# 7_Accumulator_Indicator.net
KiCad netlist of a schematic drawn in Altium Designer
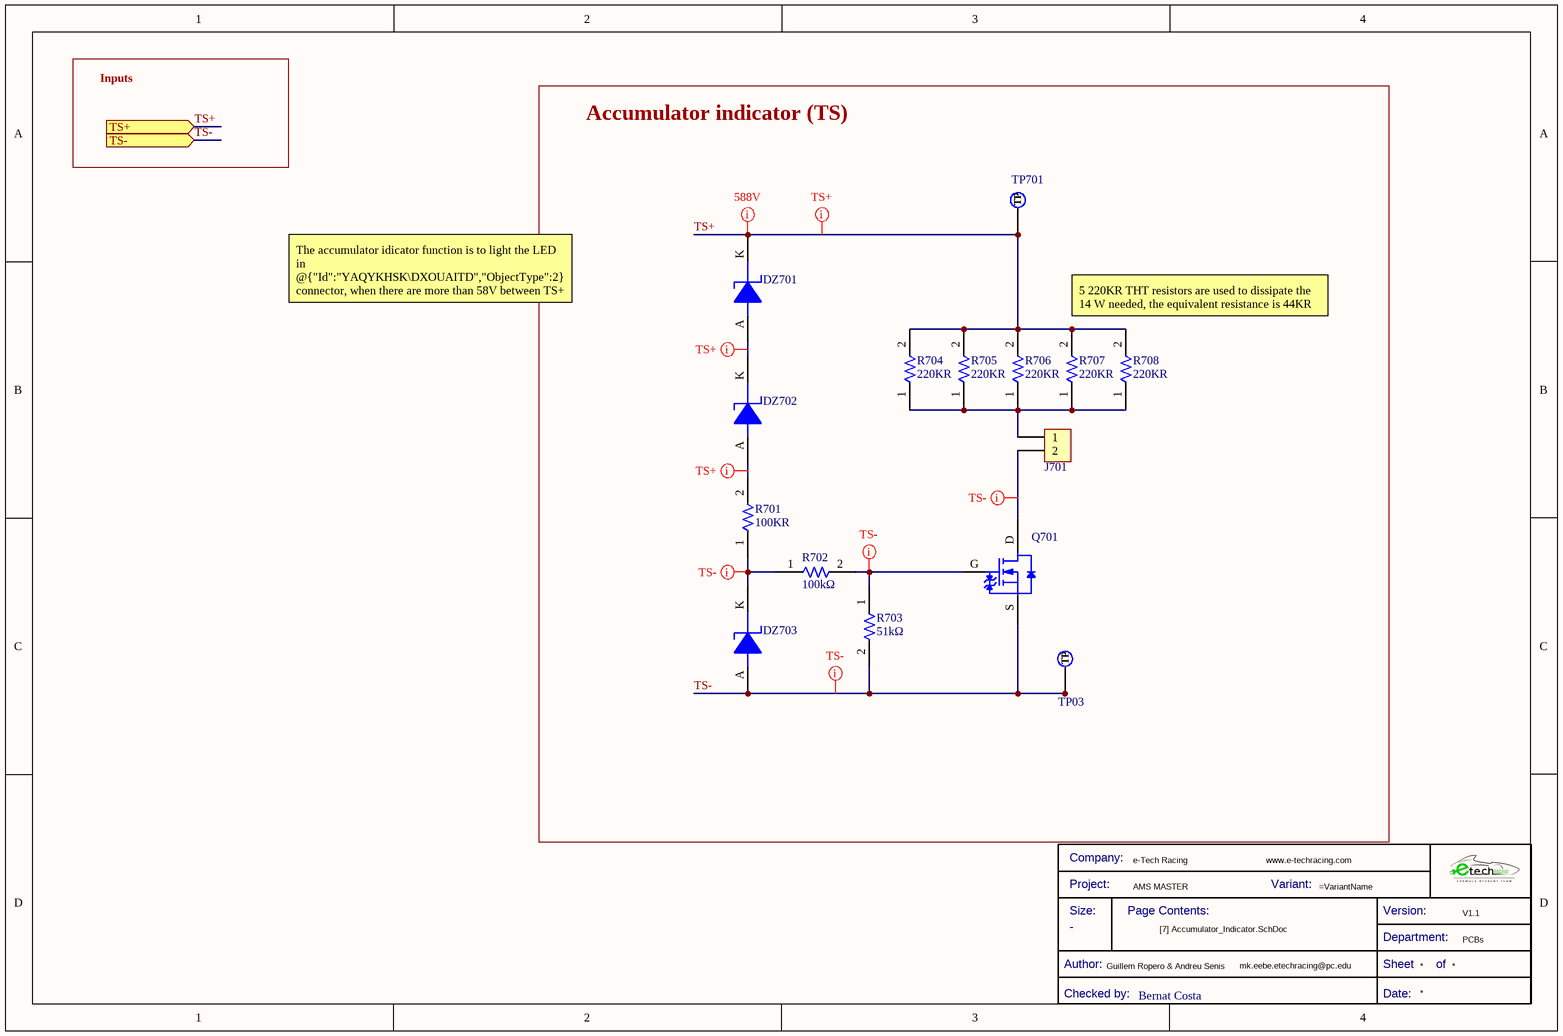
[diagram p0: [7] Accumulator_Indicator.SchDoc]

(export (version "E")
  (design (tool "Eeschema 10.0.6"))
  (components
    (comp (ref "DZ701")
      (value "DZ_24V")
      (footprint "DO214AC")
      (description "1.0 W Zener Diode Voltage Regulator 24 V")
      (fields
        (field (name "MANUFACTURER") "Diodes")
        (field (name "MANUFACTURER PART NUMBER") "BZT52C5V1-7-F")
      )
      (libsource (lib "Semiconductor") (part "DZ_24V"))
    )
    (comp (ref "DZ702")
      (value "DZ_24V")
      (footprint "DO214AC")
      (description "1.0 W Zener Diode Voltage Regulator 24 V")
      (fields
        (field (name "MANUFACTURER") "Diodes")
        (field (name "MANUFACTURER PART NUMBER") "BZT52C5V1-7-F")
      )
      (libsource (lib "Semiconductor") (part "DZ_24V"))
    )
    (comp (ref "DZ703")
      (value "DZ_10V")
      (footprint "SOD123")
      (description "BZT52C5V1 Series 500 mW 10V 10 mA Surface Mount Zener Diode - SOD-123")
      (fields
        (field (name "MANUFACTURER") "Diodes")
        (field (name "MANUFACTURER PART NUMBER") "BZT52C5V1-7-F")
      )
      (libsource (lib "Semiconductor") (part "DZ_10V"))
    )
    (comp (ref "J701")
      (value "105309-2202")
      (footprint "J_NanoFit_1x2_V")
      (fields (field (name "MANUFACTURER") "Molex"))
      (libsource (lib "Electromechanical") (part "J_Nanofit_1x2_V"))
    )
    (comp (ref "Q701")
      (value "IRLR2905")
      (footprint "IRLR2905")
      (description "MOSFET N-CH 55V 42A DPAK")
      (fields
        (field (name "MANUFACTURER") "Infineon")
        (field (name "MANUFACTURER PART NUMBER") "IRLR2905TRPBF")
      )
      (libsource (lib "Semiconductor") (part "TRT-NCH-55V-42A"))
    )
    (comp (ref "R701")
      (value "100KR")
      (footprint "THT_3W_Resistor")
      (libsource (lib "Passives") (part "R100K_3W_THT"))
    )
    (comp (ref "R702")
      (value "CRG1206F100R")
      (footprint "R1206FTK-W")
      (description "Res Thick Film 1206 100 Ohm 1% 0.25W(1/4W) ±200ppm/C Pad SMD T/R")
      (fields
        (field (name "MANUFACTURER") "TE Connectivity")
        (field (name "TOLERANCE") "1%")
        (field (name "RESISTANCE") "100kΩ")
        (field (name ".CREATOR") "AC")
      )
      (libsource (lib "Passives") (part "R100-1206FTK"))
    )
    (comp (ref "R703")
      (value "CRCW120610K0FKEA")
      (footprint "R1206FTK-W")
      (description "Res Thick Film 1206 51K Ohm 1% 1/4W ±100ppm/°C Molded SMD SMD Punched Carrier T/R")
      (fields
        (field (name "MANUFACTURER") "Panasonic")
        (field (name "MANUFACTURER PART NUMBER") "ERJ-S08F5102V")
        (field (name "RESISTANCE") "51kΩ")
        (field (name ".CREATOR") "DO")
      )
      (libsource (lib "Passives") (part "R51k-1206FTK"))
    )
    (comp (ref "R704")
      (value "220KR")
      (footprint "THT_3W_Resistor")
      (libsource (lib "Passives") (part "R220K_3W_THT"))
    )
    (comp (ref "R705")
      (value "220KR")
      (footprint "THT_3W_Resistor")
      (libsource (lib "Passives") (part "R220K_3W_THT"))
    )
    (comp (ref "R706")
      (value "220KR")
      (footprint "THT_3W_Resistor")
      (libsource (lib "Passives") (part "R220K_3W_THT"))
    )
    (comp (ref "R707")
      (value "220KR")
      (footprint "THT_3W_Resistor")
      (libsource (lib "Passives") (part "R220K_3W_THT"))
    )
    (comp (ref "R708")
      (value "220KR")
      (footprint "THT_3W_Resistor")
      (libsource (lib "Passives") (part "R220K_3W_THT"))
    )
    (comp (ref "TP03")
      (value "TestPoint")
      (footprint "TestPoint")
      (description "Test Point 1x1 mm")
      (fields (field (name ".CREATOR") "GP") (field (name ".PCBCHECK") "GP") (field (name ".SCHCHECK") "GP"))
      (libsource (lib "e-Tech_Racing") (part "TestPoint"))
    )
    (comp (ref "TP701")
      (value "TestPoint")
      (footprint "TestPoint")
      (description "Test Point 1x1 mm")
      (fields (field (name ".CREATOR") "GP") (field (name ".PCBCHECK") "GP") (field (name ".SCHCHECK") "GP"))
      (libsource (lib "e-Tech_Racing") (part "TestPoint"))
    )
  )
  (nets
    (net (code "1") (name "/TS+") (class "Default")
      (node (ref "DZ701") (pin "K") (pinfunction "K_K") (pintype "passive"))
      (node (ref "R704") (pin "2") (pinfunction "2_2") (pintype "passive"))
      (node (ref "R705") (pin "2") (pinfunction "2_2") (pintype "passive"))
      (node (ref "R706") (pin "2") (pinfunction "2_2") (pintype "passive"))
      (node (ref "R707") (pin "2") (pinfunction "2_2") (pintype "passive"))
      (node (ref "R708") (pin "2") (pinfunction "2_2") (pintype "passive"))
      (node (ref "TP701") (pin "1") (pinfunction "TP_1") (pintype "passive"))
    )
    (net (code "2") (name "/TS-") (class "Default")
      (node (ref "DZ703") (pin "A") (pinfunction "A_A") (pintype "passive"))
      (node (ref "Q701") (pin "S") (pinfunction "S_S") (pintype "passive"))
      (node (ref "R703") (pin "2") (pinfunction "2_2") (pintype "passive"))
      (node (ref "TP03") (pin "1") (pinfunction "TP_1") (pintype "passive"))
    )
    (net (code "3") (name "Net-(DZ701-PadA)") (class "Default")
      (node (ref "DZ701") (pin "A") (pinfunction "A_A") (pintype "passive"))
      (node (ref "DZ702") (pin "K") (pinfunction "K_K") (pintype "passive"))
    )
    (net (code "4") (name "Net-(DZ702-PadA)") (class "Default")
      (node (ref "DZ702") (pin "A") (pinfunction "A_A") (pintype "passive"))
      (node (ref "R701") (pin "2") (pinfunction "2_2") (pintype "passive"))
    )
    (net (code "5") (name "Net-(DZ703-PadK)") (class "Default")
      (node (ref "DZ703") (pin "K") (pinfunction "K_K") (pintype "passive"))
      (node (ref "R701") (pin "1") (pinfunction "1_1") (pintype "passive"))
      (node (ref "R702") (pin "1") (pinfunction "1_1") (pintype "passive"))
    )
    (net (code "6") (name "Net-(J701-Pad1)") (class "Default")
      (node (ref "J701") (pin "1") (pinfunction "1_1") (pintype "passive"))
      (node (ref "R704") (pin "1") (pinfunction "1_1") (pintype "passive"))
      (node (ref "R705") (pin "1") (pinfunction "1_1") (pintype "passive"))
      (node (ref "R706") (pin "1") (pinfunction "1_1") (pintype "passive"))
      (node (ref "R707") (pin "1") (pinfunction "1_1") (pintype "passive"))
      (node (ref "R708") (pin "1") (pinfunction "1_1") (pintype "passive"))
    )
    (net (code "7") (name "Net-(J701-Pad2)") (class "Default")
      (node (ref "J701") (pin "2") (pinfunction "2_2") (pintype "passive"))
      (node (ref "Q701") (pin "D") (pinfunction "D_D") (pintype "passive"))
    )
    (net (code "8") (name "Net-(Q701-PadG)") (class "Default")
      (node (ref "Q701") (pin "G") (pinfunction "G_G") (pintype "passive"))
      (node (ref "R702") (pin "2") (pinfunction "2_2") (pintype "passive"))
      (node (ref "R703") (pin "1") (pinfunction "1_1") (pintype "passive"))
    )
  )
)
